# potentiometer.net
KiCad netlist of a schematic drawn in EAGLE
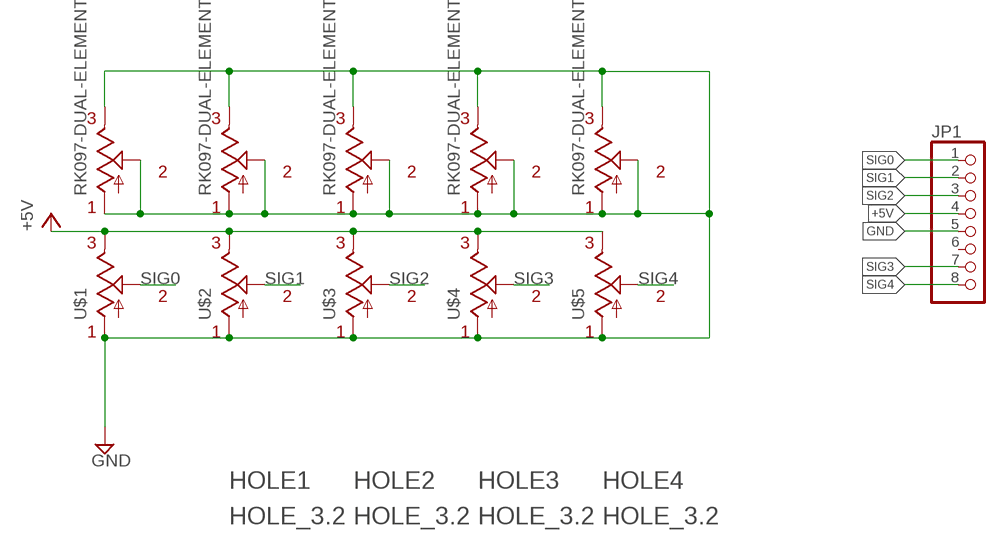
[diagram p0: schematic, sheet 1]

(export (version "E")
  (design (tool "Eeschema 10.0.6"))
  (components
    (comp (ref "HOLE1")
      (value "HOLE_3.2")
      (footprint "eagle-import:HOLE_3.2")
      (libsource (lib "eagle-import") (part "HOLE_3.2"))
    )
    (comp (ref "HOLE2")
      (value "HOLE_3.2")
      (footprint "eagle-import:HOLE_3.2")
      (libsource (lib "eagle-import") (part "HOLE_3.2"))
    )
    (comp (ref "HOLE3")
      (value "HOLE_3.2")
      (footprint "eagle-import:HOLE_3.2")
      (libsource (lib "eagle-import") (part "HOLE_3.2"))
    )
    (comp (ref "HOLE4")
      (value "HOLE_3.2")
      (footprint "eagle-import:HOLE_3.2")
      (libsource (lib "eagle-import") (part "HOLE_3.2"))
    )
    (comp (ref "JP1")
      (value "PINHD-1X8")
      (footprint "eagle-import:1X08")
      (libsource (lib "eagle-import") (part "PINHD-1X8"))
    )
    (comp (ref "U$1")
      (value "RK097-DUAL-ELEMENT")
      (footprint "eagle-import:RK097-DUAL-ELEMENT")
      (libsource (lib "eagle-import") (part "RK097-DUAL-ELEMENT"))
    )
    (comp (ref "U$2")
      (value "RK097-DUAL-ELEMENT")
      (footprint "eagle-import:RK097-DUAL-ELEMENT")
      (libsource (lib "eagle-import") (part "RK097-DUAL-ELEMENT"))
    )
    (comp (ref "U$3")
      (value "RK097-DUAL-ELEMENT")
      (footprint "eagle-import:RK097-DUAL-ELEMENT")
      (libsource (lib "eagle-import") (part "RK097-DUAL-ELEMENT"))
    )
    (comp (ref "U$4")
      (value "RK097-DUAL-ELEMENT")
      (footprint "eagle-import:RK097-DUAL-ELEMENT")
      (libsource (lib "eagle-import") (part "RK097-DUAL-ELEMENT"))
    )
    (comp (ref "U$5")
      (value "RK097-DUAL-ELEMENT")
      (footprint "eagle-import:RK097-DUAL-ELEMENT")
      (libsource (lib "eagle-import") (part "RK097-DUAL-ELEMENT"))
    )
  )
  (nets
    (net (code "1") (name "+5V") (class "Default")
      (node (ref "JP1") (pin "4") (pinfunction "4_4") (pintype "passive"))
      (node (ref "U$1") (pin "P$4") (pinfunction "E1_P$4") (pintype "passive"))
      (node (ref "U$2") (pin "P$4") (pinfunction "E1_P$4") (pintype "passive"))
      (node (ref "U$3") (pin "P$4") (pinfunction "E1_P$4") (pintype "passive"))
      (node (ref "U$4") (pin "P$4") (pinfunction "E1_P$4") (pintype "passive"))
      (node (ref "U$5") (pin "P$4") (pinfunction "E1_P$4") (pintype "passive"))
    )
    (net (code "2") (name "GND") (class "Default")
      (node (ref "JP1") (pin "5") (pinfunction "5_5") (pintype "passive"))
      (node (ref "U$1") (pin "P$1") (pinfunction "A_P$1") (pintype "passive"))
      (node (ref "U$1") (pin "P$2") (pinfunction "A1_P$2") (pintype "passive"))
      (node (ref "U$1") (pin "P$3") (pinfunction "E_P$3") (pintype "passive"))
      (node (ref "U$1") (pin "P$5") (pinfunction "S_P$5") (pintype "passive"))
      (node (ref "U$2") (pin "P$1") (pinfunction "A_P$1") (pintype "passive"))
      (node (ref "U$2") (pin "P$2") (pinfunction "A1_P$2") (pintype "passive"))
      (node (ref "U$2") (pin "P$3") (pinfunction "E_P$3") (pintype "passive"))
      (node (ref "U$2") (pin "P$5") (pinfunction "S_P$5") (pintype "passive"))
      (node (ref "U$3") (pin "P$1") (pinfunction "A_P$1") (pintype "passive"))
      (node (ref "U$3") (pin "P$2") (pinfunction "A1_P$2") (pintype "passive"))
      (node (ref "U$3") (pin "P$3") (pinfunction "E_P$3") (pintype "passive"))
      (node (ref "U$3") (pin "P$5") (pinfunction "S_P$5") (pintype "passive"))
      (node (ref "U$4") (pin "P$1") (pinfunction "A_P$1") (pintype "passive"))
      (node (ref "U$4") (pin "P$2") (pinfunction "A1_P$2") (pintype "passive"))
      (node (ref "U$4") (pin "P$3") (pinfunction "E_P$3") (pintype "passive"))
      (node (ref "U$4") (pin "P$5") (pinfunction "S_P$5") (pintype "passive"))
      (node (ref "U$5") (pin "P$1") (pinfunction "A_P$1") (pintype "passive"))
      (node (ref "U$5") (pin "P$2") (pinfunction "A1_P$2") (pintype "passive"))
      (node (ref "U$5") (pin "P$3") (pinfunction "E_P$3") (pintype "passive"))
      (node (ref "U$5") (pin "P$5") (pinfunction "S_P$5") (pintype "passive"))
    )
    (net (code "3") (name "SIG0") (class "Default")
      (node (ref "JP1") (pin "1") (pinfunction "1_1") (pintype "passive"))
      (node (ref "U$1") (pin "P$6") (pinfunction "S1_P$6") (pintype "passive"))
    )
    (net (code "4") (name "SIG1") (class "Default")
      (node (ref "JP1") (pin "2") (pinfunction "2_2") (pintype "passive"))
      (node (ref "U$2") (pin "P$6") (pinfunction "S1_P$6") (pintype "passive"))
    )
    (net (code "5") (name "SIG2") (class "Default")
      (node (ref "JP1") (pin "3") (pinfunction "3_3") (pintype "passive"))
      (node (ref "U$3") (pin "P$6") (pinfunction "S1_P$6") (pintype "passive"))
    )
    (net (code "6") (name "SIG3") (class "Default")
      (node (ref "JP1") (pin "7") (pinfunction "7_7") (pintype "passive"))
      (node (ref "U$4") (pin "P$6") (pinfunction "S1_P$6") (pintype "passive"))
    )
    (net (code "7") (name "SIG4") (class "Default")
      (node (ref "JP1") (pin "8") (pinfunction "8_8") (pintype "passive"))
      (node (ref "U$5") (pin "P$6") (pinfunction "S1_P$6") (pintype "passive"))
    )
    (net (code "8") (name "unconnected-(JP1-Pad6)") (class "Default")
      (node (ref "JP1") (pin "6") (pinfunction "6_6") (pintype "passive"))
    )
  )
)
